# Reset.net
KiCad netlist of a schematic drawn in Altium Designer
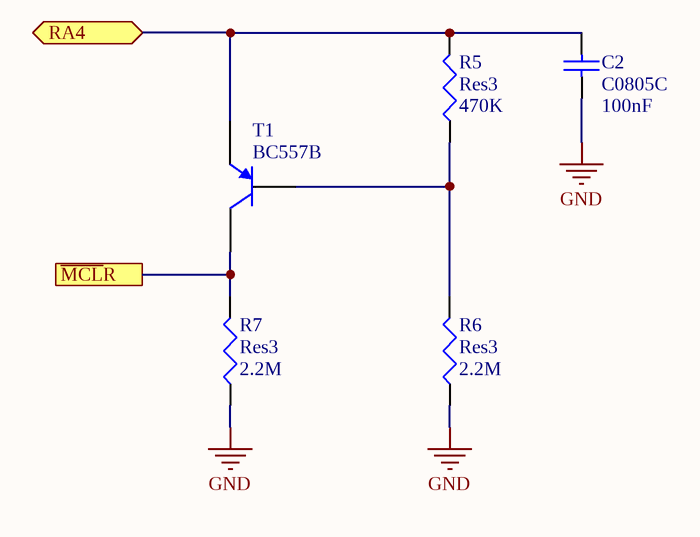
[diagram p0: Reset.SchDoc]

(export (version "E")
  (design (tool "Eeschema 10.0.6"))
  (components
    (comp (ref "C2")
      (value "C0805C")
      (footprint "0805")
      (description "Ceramic Chip Capacitor - Standard")
      (fields (field (name "ALTIUM_VALUE") "100nF") (field (name "PUBLISHER") "Altium Limited"))
      (libsource (lib "KEMET Chip Capacitor") (part "C0805"))
    )
    (comp (ref "R5")
      (value "Res3")
      (footprint "J1-0603")
      (description "Resistor")
      (fields (field (name "ALTIUM_VALUE") "470K") (field (name "PUBLISHER") "Altium Limited"))
      (libsource (lib "Miscellaneous Devices") (part "Res3"))
    )
    (comp (ref "R6")
      (value "Res3")
      (footprint "J1-0603")
      (description "Resistor")
      (fields (field (name "ALTIUM_VALUE") "2.2M") (field (name "PUBLISHER") "Altium Limited"))
      (libsource (lib "Miscellaneous Devices") (part "Res3"))
    )
    (comp (ref "R7")
      (value "Res3")
      (footprint "J1-0603")
      (description "Resistor")
      (fields (field (name "ALTIUM_VALUE") "2.2M") (field (name "PUBLISHER") "Altium Limited"))
      (libsource (lib "Miscellaneous Devices") (part "Res3"))
    )
    (comp (ref "T1")
      (value "BC557B")
      (footprint "29-04")
      (description "Amplifier Transistor PNP Silicon")
      (fields (field (name "PUBLISHER") "Altium Limited"))
      (libsource (lib "Motorola Discrete BJT") (part "BC557B"))
    )
  )
  (nets
    (net (code "1") (name "/RA4") (class "Default")
      (node (ref "C2") (pin "2") (pinfunction "2_2") (pintype "passive"))
      (node (ref "R5") (pin "2") (pinfunction "2_2") (pintype "passive"))
      (node (ref "T1") (pin "3") (pinfunction "E_3") (pintype "passive"))
    )
    (net (code "2") (name "/~{MCL}R") (class "Default")
      (node (ref "R7") (pin "2") (pinfunction "2_2") (pintype "passive"))
      (node (ref "T1") (pin "1") (pinfunction "C_1") (pintype "passive"))
    )
    (net (code "3") (name "GND") (class "Default")
      (node (ref "C2") (pin "1") (pinfunction "1_1") (pintype "passive"))
      (node (ref "R6") (pin "1") (pinfunction "1_1") (pintype "passive"))
      (node (ref "R7") (pin "1") (pinfunction "1_1") (pintype "passive"))
    )
    (net (code "4") (name "Net-(T1-B)") (class "Default")
      (node (ref "R5") (pin "1") (pinfunction "1_1") (pintype "passive"))
      (node (ref "R6") (pin "2") (pinfunction "2_2") (pintype "passive"))
      (node (ref "T1") (pin "2") (pinfunction "B_2") (pintype "passive"))
    )
  )
)
